# projet_pcb_etu_formatA4.net
KiCad netlist of a schematic drawn in Altium Designer
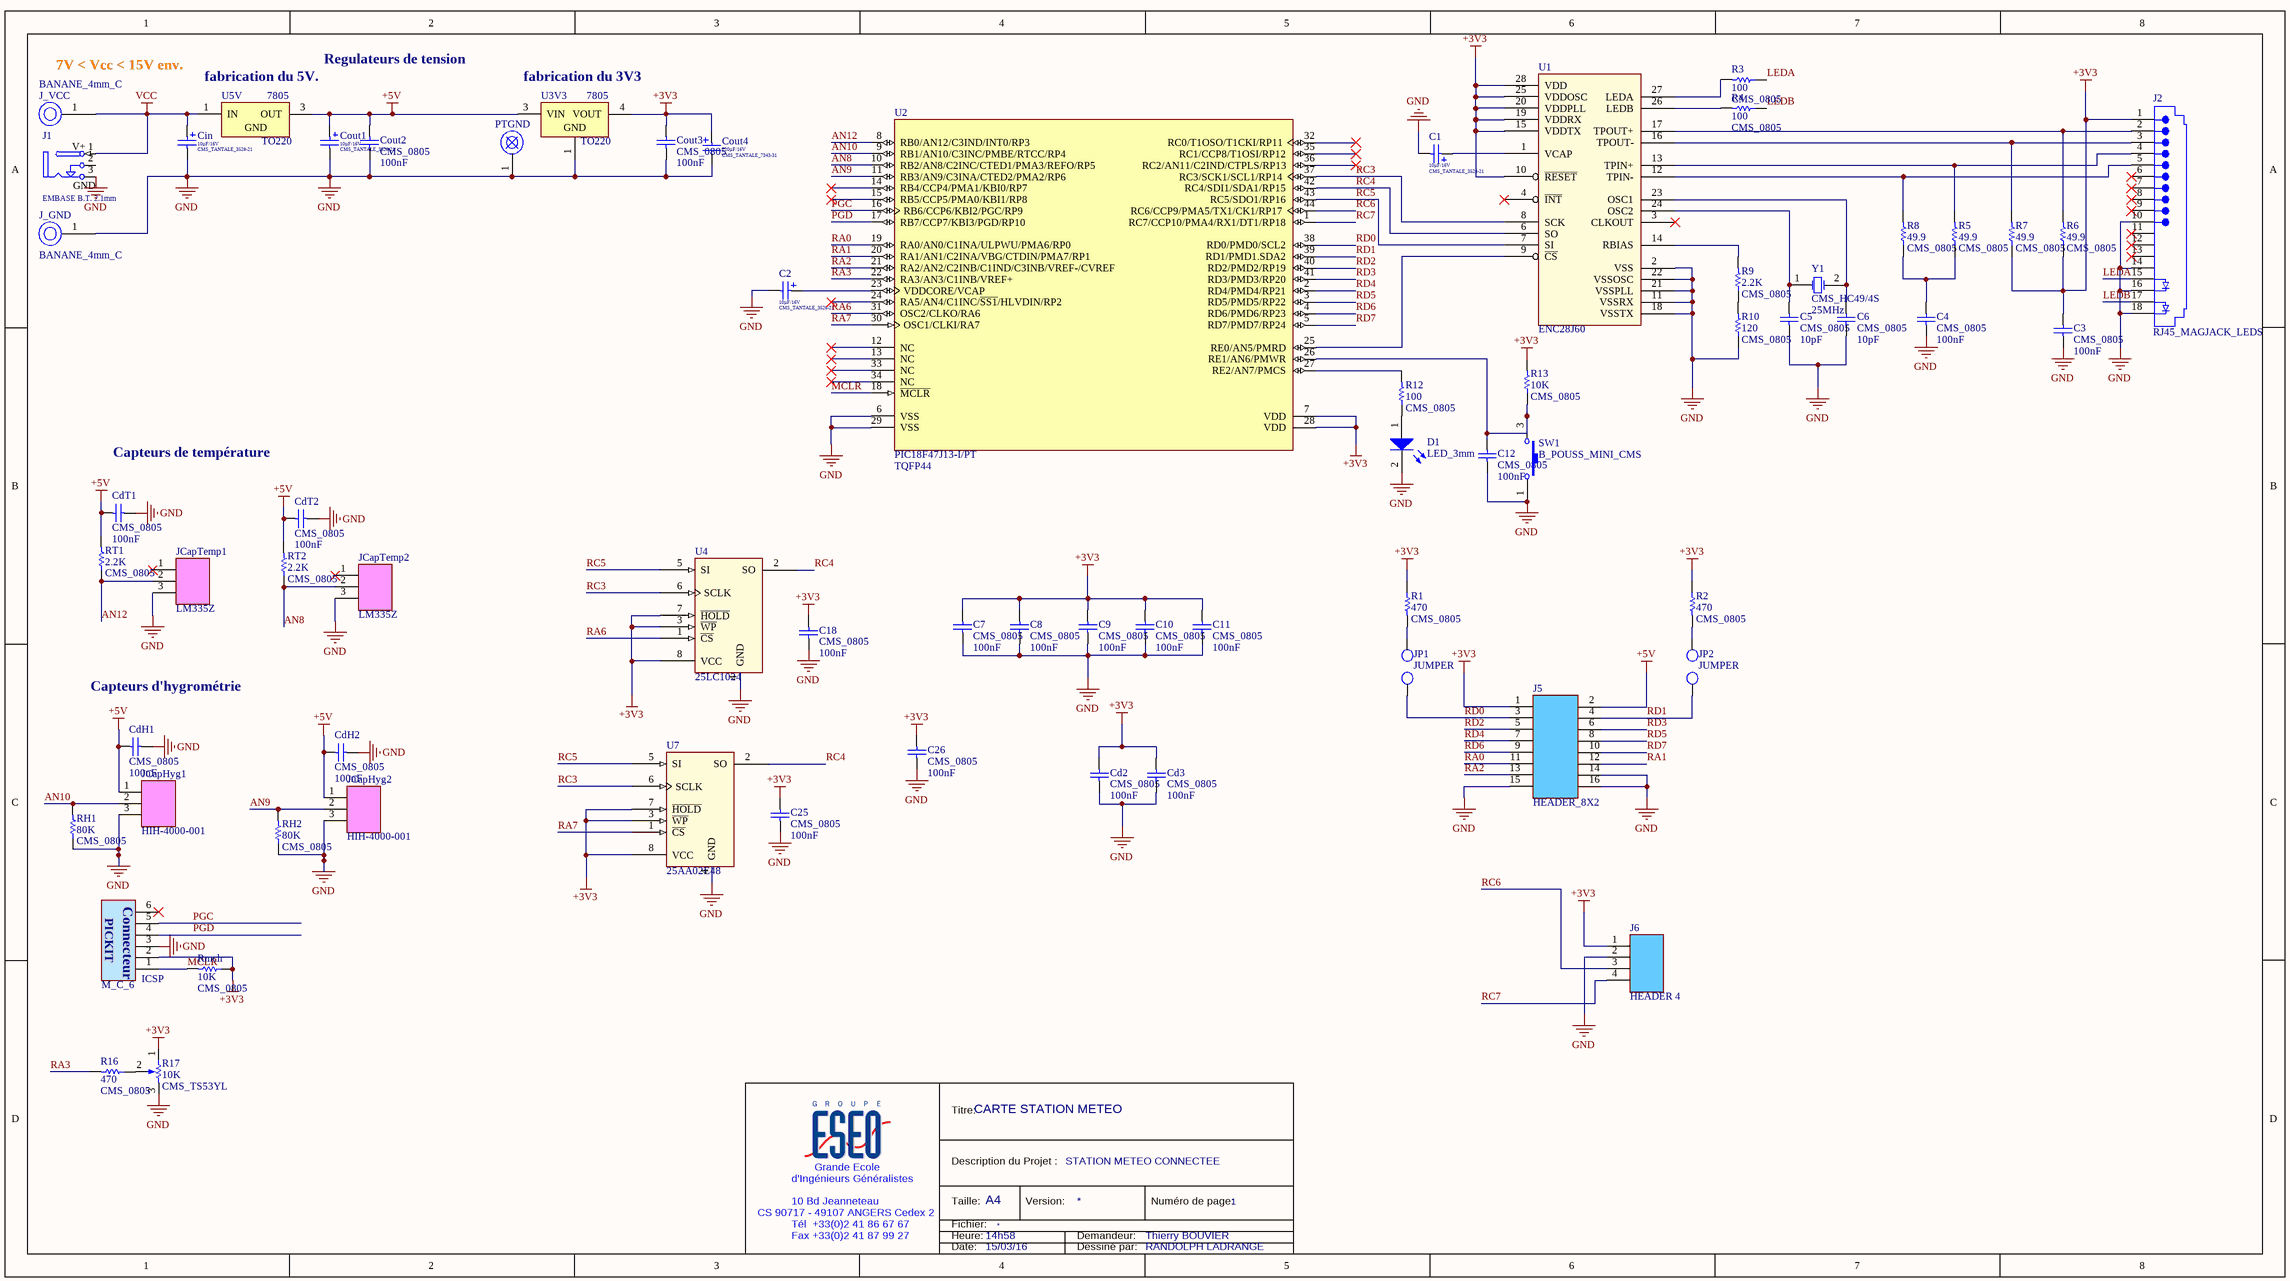
[diagram p0: projet_pcb_etu_formatA4.SchDoc]

(export (version "E")
  (design (tool "Eeschema 10.0.6"))
  (components
    (comp (ref "C1")
      (value "10µF/16V")
      (footprint "CONDENSATEUR_CMS_POLARISE_TANTALE_B/3528-21")
      (description "CONDENSATEUR CMS POLARISE TANTALE BOITIER B/3528-21")
      (fields
        (field (name "TYPE") "CMS_TANTALE_3528-21")
        (field (name "Comment") "CMS_POLARISE_TANTALE_3528-21")
      )
      (libsource (lib "composants passifs") (part "CONDENSATEUR_CMS_POL_TANT_B_3528-21"))
    )
    (comp (ref "C2")
      (value "10µF/16V")
      (footprint "CONDENSATEUR_CMS_POLARISE_TANTALE_B/3528-21")
      (description "CONDENSATEUR CMS POLARISE TANTALE BOITIER B/3528-21")
      (fields
        (field (name "TYPE") "CMS_TANTALE_3528-21")
        (field (name "Comment") "CMS_POLARISE_TANTALE_3528-21")
      )
      (libsource (lib "composants passifs") (part "CONDENSATEUR_CMS_POL_TANT_B_3528-21"))
    )
    (comp (ref "C3")
      (value "100nF")
      (footprint "CONDENSATEUR_CMS_0805")
      (description "CONDENSATEUR CMS CERAMIQUE 0805")
      (fields (field (name "TYPE") "CMS_0805") (field (name "Comment") "CMS_0805"))
      (libsource (lib "composants passifs") (part "CONDENSATEUR_CMS_CER_0805"))
    )
    (comp (ref "C4")
      (value "100nF")
      (footprint "CONDENSATEUR_CMS_0805")
      (description "CONDENSATEUR CMS CERAMIQUE 0805")
      (fields (field (name "TYPE") "CMS_0805") (field (name "Comment") "CMS_0805"))
      (libsource (lib "composants passifs") (part "CONDENSATEUR_CMS_CER_0805"))
    )
    (comp (ref "C5")
      (value "10pF")
      (footprint "CONDENSATEUR_CMS_0805")
      (description "CONDENSATEUR CMS CERAMIQUE 0805")
      (fields (field (name "TYPE") "CMS_0805") (field (name "Comment") "CMS_0805"))
      (libsource (lib "composants passifs") (part "CONDENSATEUR_CMS_CER_0805"))
    )
    (comp (ref "C6")
      (value "10pF")
      (footprint "CONDENSATEUR_CMS_0805")
      (description "CONDENSATEUR CMS CERAMIQUE 0805")
      (fields (field (name "TYPE") "CMS_0805") (field (name "Comment") "CMS_0805"))
      (libsource (lib "composants passifs") (part "CONDENSATEUR_CMS_CER_0805"))
    )
    (comp (ref "C7")
      (value "100nF")
      (footprint "CONDENSATEUR_CMS_0805")
      (description "CONDENSATEUR CMS CERAMIQUE 0805")
      (fields (field (name "TYPE") "CMS_0805") (field (name "Comment") "CMS_0805"))
      (libsource (lib "composants passifs") (part "CONDENSATEUR_CMS_CER_0805"))
    )
    (comp (ref "C8")
      (value "100nF")
      (footprint "CONDENSATEUR_CMS_0805")
      (description "CONDENSATEUR CMS CERAMIQUE 0805")
      (fields (field (name "TYPE") "CMS_0805") (field (name "Comment") "CMS_0805"))
      (libsource (lib "composants passifs") (part "CONDENSATEUR_CMS_CER_0805"))
    )
    (comp (ref "C9")
      (value "100nF")
      (footprint "CONDENSATEUR_CMS_0805")
      (description "CONDENSATEUR CMS CERAMIQUE 0805")
      (fields (field (name "TYPE") "CMS_0805") (field (name "Comment") "CMS_0805"))
      (libsource (lib "composants passifs") (part "CONDENSATEUR_CMS_CER_0805"))
    )
    (comp (ref "C10")
      (value "100nF")
      (footprint "CONDENSATEUR_CMS_0805")
      (description "CONDENSATEUR CMS CERAMIQUE 0805")
      (fields (field (name "TYPE") "CMS_0805") (field (name "Comment") "CMS_0805"))
      (libsource (lib "composants passifs") (part "CONDENSATEUR_CMS_CER_0805"))
    )
    (comp (ref "C11")
      (value "100nF")
      (footprint "CONDENSATEUR_CMS_0805")
      (description "CONDENSATEUR CMS CERAMIQUE 0805")
      (fields (field (name "TYPE") "CMS_0805") (field (name "Comment") "CMS_0805"))
      (libsource (lib "composants passifs") (part "CONDENSATEUR_CMS_CER_0805"))
    )
    (comp (ref "C12")
      (value "100nF")
      (footprint "CONDENSATEUR_CMS_0805")
      (description "CONDENSATEUR CMS CERAMIQUE 0805")
      (fields (field (name "TYPE") "CMS_0805") (field (name "Comment") "CMS_0805"))
      (libsource (lib "composants passifs") (part "CONDENSATEUR_CMS_CER_0805"))
    )
    (comp (ref "C18")
      (value "100nF")
      (footprint "CONDENSATEUR_CMS_0805")
      (description "CONDENSATEUR CMS CERAMIQUE 0805")
      (fields (field (name "TYPE") "CMS_0805") (field (name "Comment") "CMS_0805"))
      (libsource (lib "composants passifs") (part "CONDENSATEUR_CMS_CER_0805"))
    )
    (comp (ref "C25")
      (value "100nF")
      (footprint "CONDENSATEUR_CMS_0805")
      (description "CONDENSATEUR CMS CERAMIQUE 0805")
      (fields (field (name "TYPE") "CMS_0805") (field (name "Comment") "CMS_0805"))
      (libsource (lib "composants passifs") (part "CONDENSATEUR_CMS_CER_0805"))
    )
    (comp (ref "C26")
      (value "100nF")
      (footprint "CONDENSATEUR_CMS_0805")
      (description "CONDENSATEUR CMS CERAMIQUE 0805")
      (fields (field (name "TYPE") "CMS_0805") (field (name "Comment") "CMS_0805"))
      (libsource (lib "composants passifs") (part "CONDENSATEUR_CMS_CER_0805"))
    )
    (comp (ref "Cd2")
      (value "100nF")
      (footprint "CONDENSATEUR_CMS_0805")
      (description "CONDENSATEUR CMS CERAMIQUE 0805")
      (fields (field (name "TYPE") "CMS_0805") (field (name "Comment") "CMS_0805"))
      (libsource (lib "composants passifs") (part "CONDENSATEUR_CMS_CER_0805"))
    )
    (comp (ref "Cd3")
      (value "100nF")
      (footprint "CONDENSATEUR_CMS_0805")
      (description "CONDENSATEUR CMS CERAMIQUE 0805")
      (fields (field (name "TYPE") "CMS_0805") (field (name "Comment") "CMS_0805"))
      (libsource (lib "composants passifs") (part "CONDENSATEUR_CMS_CER_0805"))
    )
    (comp (ref "CdH1")
      (value "100nF")
      (footprint "CONDENSATEUR_CMS_0805")
      (description "CONDENSATEUR CMS CERAMIQUE 0805")
      (fields (field (name "TYPE") "CMS_0805") (field (name "Comment") "CMS_0805"))
      (libsource (lib "composants passifs") (part "CONDENSATEUR_CMS_CER_0805"))
    )
    (comp (ref "CdH2")
      (value "100nF")
      (footprint "CONDENSATEUR_CMS_0805")
      (description "CONDENSATEUR CMS CERAMIQUE 0805")
      (fields (field (name "TYPE") "CMS_0805") (field (name "Comment") "CMS_0805"))
      (libsource (lib "composants passifs") (part "CONDENSATEUR_CMS_CER_0805"))
    )
    (comp (ref "CdT1")
      (value "100nF")
      (footprint "CONDENSATEUR_CMS_0805")
      (description "CONDENSATEUR CMS CERAMIQUE 0805")
      (fields (field (name "TYPE") "CMS_0805") (field (name "Comment") "CMS_0805"))
      (libsource (lib "composants passifs") (part "CONDENSATEUR_CMS_CER_0805"))
    )
    (comp (ref "CdT2")
      (value "100nF")
      (footprint "CONDENSATEUR_CMS_0805")
      (description "CONDENSATEUR CMS CERAMIQUE 0805")
      (fields (field (name "TYPE") "CMS_0805") (field (name "Comment") "CMS_0805"))
      (libsource (lib "composants passifs") (part "CONDENSATEUR_CMS_CER_0805"))
    )
    (comp (ref "Cin")
      (value "10µF/16V")
      (footprint "composants passifs:CONDENSATEUR_CMS_POLARISE_TANTALE_B/3528-21")
      (description "CONDENSATEUR CMS POLARISE TANTALE BOITIER B/3528-21")
      (fields
        (field (name "TYPE") "CMS_TANTALE_3528-21")
        (field (name "Comment") "CMS_POLARISE_TANTALE_3528-21")
      )
      (libsource (lib "composants passifs") (part "CONDENSATEUR_CMS_POL_TANT_B_3528-21"))
    )
    (comp (ref "Cout1")
      (value "10µF/16V")
      (footprint "composants passifs:CONDENSATEUR_CMS_POLARISE_TANTALE_B/3528-21")
      (description "CONDENSATEUR CMS POLARISE TANTALE BOITIER B/3528-21")
      (fields
        (field (name "TYPE") "CMS_TANTALE_3528-21")
        (field (name "Comment") "CMS_POLARISE_TANTALE_3528-21")
      )
      (libsource (lib "composants passifs") (part "CONDENSATEUR_CMS_POL_TANT_B_3528-21"))
    )
    (comp (ref "Cout2")
      (value "100nF")
      (footprint "CONDENSATEUR_CMS_0805")
      (description "CONDENSATEUR CMS CERAMIQUE 0805")
      (fields (field (name "TYPE") "CMS_0805") (field (name "Comment") "CMS_0805"))
      (libsource (lib "composants passifs") (part "CONDENSATEUR_CMS_CER_0805"))
    )
    (comp (ref "Cout3")
      (value "100nF")
      (footprint "CONDENSATEUR_CMS_0805")
      (description "CONDENSATEUR CMS CERAMIQUE 0805")
      (fields (field (name "TYPE") "CMS_0805") (field (name "Comment") "CMS_0805"))
      (libsource (lib "composants passifs") (part "CONDENSATEUR_CMS_CER_0805"))
    )
    (comp (ref "Cout4")
      (value "220µF/16V")
      (footprint "CONDENSATEUR_CMS_POLARISE_TANTALE_D/7343-31")
      (description "CONDENSATEUR CMS POLARISE TANTALE BOITIER D/7343-31")
      (fields
        (field (name "TYPE") "CMS_TANTALE_7343-31")
        (field (name "Comment") "CMS_POLARISE_TANTALE_7343-31")
      )
      (libsource (lib "composants passifs") (part "CONDENSATEUR_CMS_POL_TANT_D_7343-31"))
    )
    (comp (ref "D1")
      (value "LED_3MM")
      (footprint "LED_3MM")
      (description "LED 3MM - ROUGE/VERTE/JAUNE")
      (fields (field (name "TYPE") "LED_3mm"))
      (libsource (lib "affichage") (part "LED_3MM"))
    )
    (comp (ref "ICSP")
      (value "BARRETTE_6 CONTACTS_1 RANGEE_MALE_COUDEE")
      (footprint "BARRETTE_6_M_C")
      (description "BARRETTE 6 CONTACTS 1 RANGEE MALE COUDEE")
      (fields (field (name "TYPE") "M_C_6"))
      (libsource (lib "connecteurs") (part "BARRETTE_6 CONTACTS_1 RANGEE_MALE_COUDEE"))
    )
    (comp (ref "J1")
      (value "EMBASE_BASSE_TENSION_2.1mm")
      (footprint "EMBASE_BASSE_TENSION_2.1mm")
      (description "EMBASE BASSE TENSION 2.1mm")
      (fields (field (name "TYPE") "EMBASE B.T. 2.1mm"))
      (libsource (lib "connecteurs") (part "EMBASE_BASSE_TENSION_2.1mm"))
    )
    (comp (ref "J2")
      (value "RJ45_MAGJACK_LEDS")
      (footprint "RJ45_MAGJACK_LED")
      (description "EMBASE RJ45_MAGJACK_LEDS")
      (fields (field (name "TYPE") "RJ45_MAGJACK_LEDS"))
      (libsource (lib "connecteurs") (part "RJ45_MAGJACK_LEDS"))
    )
    (comp (ref "J5")
      (value "BARRETTE_8 CONTACTS_2 RANGEES_MALE_DROITE")
      (footprint "BARRETTE_8X2_M_D")
      (fields (field (name "TYPE") "HEADER_8X2"))
      (libsource (lib "connecteurs") (part "BARRETTE_8 CONTACTS_2 RANGEES_MALE_DROITE"))
    )
    (comp (ref "J6")
      (value "BARRETTE_4 CONTACTS_1 RANGEE_MALE_DROITE")
      (footprint "BARRETTE_4_M_D")
      (description "BARRETTE 4 CONTACTS 1 RANGEE MALE DROITE")
      (fields (field (name "TYPE") "HEADER 4"))
      (libsource (lib "connecteurs") (part "BARRETTE_4 CONTACTS_1 RANGEE_MALE_DROITE"))
    )
    (comp (ref "JCapHyg1")
      (value "BARRETTE 3 CONTACTS 1 RANGEE FEMELLE DROITE")
      (footprint "BARRETTE_3_F_D")
      (fields (field (name "TYPE") "HIH-4000-001"))
      (libsource (lib "connecteurs") (part "BARRETTE_3 CONTACTS_1 RANGEE_FEMELLE_DROITE"))
    )
    (comp (ref "JCapHyg2")
      (value "BARRETTE 3 CONTACTS 1 RANGEE FEMELLE DROITE")
      (footprint "BARRETTE_3_F_D")
      (fields (field (name "TYPE") "HIH-4000-001"))
      (libsource (lib "connecteurs") (part "BARRETTE_3 CONTACTS_1 RANGEE_FEMELLE_DROITE"))
    )
    (comp (ref "JCapTemp1")
      (value "BARRETTE 3 CONTACTS 1 RANGEE FEMELLE DROITE")
      (footprint "BARRETTE_3_F_D")
      (fields (field (name "TYPE") "LM335Z"))
      (libsource (lib "connecteurs") (part "BARRETTE_3 CONTACTS_1 RANGEE_FEMELLE_DROITE"))
    )
    (comp (ref "JCapTemp2")
      (value "BARRETTE 3 CONTACTS 1 RANGEE FEMELLE DROITE")
      (footprint "BARRETTE_3_F_D")
      (fields (field (name "TYPE") "LM335Z"))
      (libsource (lib "connecteurs") (part "BARRETTE_3 CONTACTS_1 RANGEE_FEMELLE_DROITE"))
    )
    (comp (ref "JP1")
      (value "JUMPER2")
      (footprint "BARRETTE_2_M_D")
      (description "BARRETTE 2 CONTACTS 1 RANGEE MALE DROITE")
      (fields (field (name "TYPE") "JUMPER"))
      (libsource (lib "connecteurs") (part "JUMPER2"))
    )
    (comp (ref "JP2")
      (value "JUMPER2")
      (footprint "BARRETTE_2_M_D")
      (description "BARRETTE 2 CONTACTS 1 RANGEE MALE DROITE")
      (fields (field (name "TYPE") "JUMPER"))
      (libsource (lib "connecteurs") (part "JUMPER2"))
    )
    (comp (ref "J_GND")
      (value "DOUILLE BANANE 4mm COUDEE")
      (footprint "DOUILLE_BANANE_4MM_COUDEE")
      (description "DOUILLE BANANE 4 mm COUDEE")
      (fields (field (name "TYPE") "BANANE_4mm_C"))
      (libsource (lib "connecteurs") (part "DOUILLE_BANANE_4mm_COUDEE"))
    )
    (comp (ref "J_VCC")
      (value "DOUILLE BANANE 4mm COUDEE")
      (footprint "DOUILLE_BANANE_4MM_COUDEE")
      (description "DOUILLE BANANE 4 mm COUDEE")
      (fields (field (name "TYPE") "BANANE_4mm_C"))
      (libsource (lib "connecteurs") (part "DOUILLE_BANANE_4mm_COUDEE"))
    )
    (comp (ref "PTGND")
      (value "POINT_TEST")
      (footprint "POINT_TEST")
      (description "POINT TEST")
      (libsource (lib "connecteurs") (part "POINT_TEST"))
    )
    (comp (ref "R1")
      (value "470")
      (footprint "RESISTANCE_CMS_0805")
      (description "RESISTANCE CMS 0805")
      (fields (field (name "TYPE") "CMS_0805") (field (name "Comment") "RESISTANCE_CMS_0805"))
      (libsource (lib "composants passifs") (part "RESISTANCE_CMS_0805"))
    )
    (comp (ref "R2")
      (value "470")
      (footprint "RESISTANCE_CMS_0805")
      (description "RESISTANCE CMS 0805")
      (fields (field (name "TYPE") "CMS_0805") (field (name "Comment") "RESISTANCE_CMS_0805"))
      (libsource (lib "composants passifs") (part "RESISTANCE_CMS_0805"))
    )
    (comp (ref "R3")
      (value "100")
      (footprint "RESISTANCE_CMS_0805")
      (description "RESISTANCE CMS 0805")
      (fields (field (name "TYPE") "CMS_0805") (field (name "Comment") "RESISTANCE_CMS_0805"))
      (libsource (lib "composants passifs") (part "RESISTANCE_CMS_0805"))
    )
    (comp (ref "R4")
      (value "100")
      (footprint "RESISTANCE_CMS_0805")
      (description "RESISTANCE CMS 0805")
      (fields (field (name "TYPE") "CMS_0805") (field (name "Comment") "RESISTANCE_CMS_0805"))
      (libsource (lib "composants passifs") (part "RESISTANCE_CMS_0805"))
    )
    (comp (ref "R5")
      (value "49.9")
      (footprint "RESISTANCE_CMS_0805")
      (description "RESISTANCE CMS 0805")
      (fields (field (name "TYPE") "CMS_0805") (field (name "Comment") "RESISTANCE_CMS_0805"))
      (libsource (lib "composants passifs") (part "RESISTANCE_CMS_0805"))
    )
    (comp (ref "R6")
      (value "49.9")
      (footprint "RESISTANCE_CMS_0805")
      (description "RESISTANCE CMS 0805")
      (fields (field (name "TYPE") "CMS_0805") (field (name "Comment") "RESISTANCE_CMS_0805"))
      (libsource (lib "composants passifs") (part "RESISTANCE_CMS_0805"))
    )
    (comp (ref "R7")
      (value "49.9")
      (footprint "RESISTANCE_CMS_0805")
      (description "RESISTANCE CMS 0805")
      (fields (field (name "TYPE") "CMS_0805") (field (name "Comment") "RESISTANCE_CMS_0805"))
      (libsource (lib "composants passifs") (part "RESISTANCE_CMS_0805"))
    )
    (comp (ref "R8")
      (value "49.9")
      (footprint "RESISTANCE_CMS_0805")
      (description "RESISTANCE CMS 0805")
      (fields (field (name "TYPE") "CMS_0805") (field (name "Comment") "RESISTANCE_CMS_0805"))
      (libsource (lib "composants passifs") (part "RESISTANCE_CMS_0805"))
    )
    (comp (ref "R9")
      (value "2.2K")
      (footprint "RESISTANCE_CMS_0805")
      (description "RESISTANCE CMS 0805")
      (fields (field (name "TYPE") "CMS_0805") (field (name "Comment") "RESISTANCE_CMS_0805"))
      (libsource (lib "composants passifs") (part "RESISTANCE_CMS_0805"))
    )
    (comp (ref "R10")
      (value "120")
      (footprint "RESISTANCE_CMS_0805")
      (description "RESISTANCE CMS 0805")
      (fields (field (name "TYPE") "CMS_0805") (field (name "Comment") "RESISTANCE_CMS_0805"))
      (libsource (lib "composants passifs") (part "RESISTANCE_CMS_0805"))
    )
    (comp (ref "R12")
      (value "100")
      (footprint "RESISTANCE_CMS_0805")
      (description "RESISTANCE CMS 0805")
      (fields (field (name "TYPE") "CMS_0805") (field (name "Comment") "RESISTANCE_CMS_0805"))
      (libsource (lib "composants passifs") (part "RESISTANCE_CMS_0805"))
    )
    (comp (ref "R13")
      (value "10K")
      (footprint "RESISTANCE_CMS_0805")
      (description "RESISTANCE CMS 0805")
      (fields (field (name "TYPE") "CMS_0805") (field (name "Comment") "RESISTANCE_CMS_0805"))
      (libsource (lib "composants passifs") (part "RESISTANCE_CMS_0805"))
    )
    (comp (ref "R16")
      (value "470")
      (footprint "RESISTANCE_CMS_0805")
      (description "RESISTANCE CMS 0805")
      (fields (field (name "TYPE") "CMS_0805") (field (name "Comment") "RESISTANCE_CMS_0805"))
      (libsource (lib "composants passifs") (part "RESISTANCE_CMS_0805"))
    )
    (comp (ref "R17")
      (value "10K")
      (footprint "TRIMMER_CMS_TS53YL")
      (description "RESISTANCE VARIABLE_CMS : TS53YL")
      (fields (field (name "TYPE") "CMS_TS53YL") (field (name "Comment") "RESISTANCE_VARIABLE_CMS : TS53YL"))
      (libsource (lib "composants passifs") (part "RESISTANCE_VARIABLE_CMS {colon} TS53YL"))
    )
    (comp (ref "RH1")
      (value "80K")
      (footprint "RESISTANCE_CMS_0805")
      (description "RESISTANCE CMS 0805")
      (fields (field (name "TYPE") "CMS_0805") (field (name "Comment") "RESISTANCE_CMS_0805"))
      (libsource (lib "composants passifs") (part "RESISTANCE_CMS_0805"))
    )
    (comp (ref "RH2")
      (value "80K")
      (footprint "RESISTANCE_CMS_0805")
      (description "RESISTANCE CMS 0805")
      (fields (field (name "TYPE") "CMS_0805") (field (name "Comment") "RESISTANCE_CMS_0805"))
      (libsource (lib "composants passifs") (part "RESISTANCE_CMS_0805"))
    )
    (comp (ref "Rmclr")
      (value "10K")
      (footprint "RESISTANCE_CMS_0805")
      (description "RESISTANCE CMS 0805")
      (fields (field (name "TYPE") "CMS_0805") (field (name "Comment") "RESISTANCE_CMS_0805"))
      (libsource (lib "composants passifs") (part "RESISTANCE_CMS_0805"))
    )
    (comp (ref "RT1")
      (value "2.2K")
      (footprint "RESISTANCE_CMS_0805")
      (description "RESISTANCE CMS 0805")
      (fields (field (name "TYPE") "CMS_0805") (field (name "Comment") "RESISTANCE_CMS_0805"))
      (libsource (lib "composants passifs") (part "RESISTANCE_CMS_0805"))
    )
    (comp (ref "RT2")
      (value "2.2K")
      (footprint "RESISTANCE_CMS_0805")
      (description "RESISTANCE CMS 0805")
      (fields (field (name "TYPE") "CMS_0805") (field (name "Comment") "RESISTANCE_CMS_0805"))
      (libsource (lib "composants passifs") (part "RESISTANCE_CMS_0805"))
    )
    (comp (ref "SW1")
      (value "BOUTON_POUSSOIR_MINIATURE_CMS")
      (footprint "BOUTON_POUSS_CMS")
      (description "BOUTON POUSSOIR MINIATURE CMS ON/OFF")
      (fields (field (name "TYPE") "B_POUSS_MINI_CMS"))
      (libsource (lib "commutation") (part "BOUTON_POUSSOIR_MINIATURE_CMS"))
    )
    (comp (ref "U1")
      (value "ENC28J60")
      (footprint "circuits integres:SOIC28_PAS=1.27_LARG=10.3_LONG=18")
      (libsource (lib "circuits integres") (part "ENC28J60"))
    )
    (comp (ref "U2")
      (value "PIC18F47J13-I/PT_TQFP44")
      (footprint "TQFP44_PAS=0.8_LARG=12_LONG=12")
      (fields (field (name "TYPE") "PIC18F47J13-I/PT") (field (name "PACKAGE") "TQFP44"))
      (libsource (lib "circuits integres") (part "PIC18F47J13-I/PT_TQFP44"))
    )
    (comp (ref "U3V3")
      (value "REGULATEUR_TO220_78XX")
      (footprint "composants actifs:TO-252")
      (description "REGULATEUR DE TENSION POSITIVE 78XX BOITIER TO220")
      (fields (field (name "TYPE") "7805") (field (name "PACKAGE") "TO220"))
      (libsource (lib "") (part "REGULATEUR_TO220_78XX_1"))
    )
    (comp (ref "U4")
      (value "25LC1024")
      (footprint "SOP8_PAS=1.27_LARG=6_LONG=5.2")
      (libsource (lib "circuits integres") (part "25LC1024"))
    )
    (comp (ref "U5V")
      (value "REGULATEUR_TO220_78XX")
      (footprint "composants actifs:TO-252")
      (description "REGULATEUR DE TENSION POSITIVE 78XX BOITIER TO220")
      (fields (field (name "TYPE") "7805") (field (name "PACKAGE") "TO220"))
      (libsource (lib "composants actifs") (part "REGULATEUR_TO220_78XX"))
    )
    (comp (ref "U7")
      (value "25AA02E48")
      (footprint "SOIC8_PAS=1.27_LARG=4_LONG=5")
      (libsource (lib "circuits integres") (part "25AA02E48"))
    )
    (comp (ref "Y1")
      (value "25MHz")
      (footprint "QUARTZ_CMS_HC49/4S")
      (description "QUARTZ CMS HC49/4S")
      (fields (field (name "TYPE") "CMS_HC49/4S") (field (name "Comment") "QUARTZ_CMS_HC49/4S"))
      (libsource (lib "composants passifs") (part "QUARTZ_CMS_HC49/4S"))
    )
  )
  (nets
    (net (code "1") (name "+3V3") (class "Default")
      (node (ref "C10") (pin "1") (pinfunction "1_1") (pintype "passive"))
      (node (ref "C11") (pin "1") (pinfunction "1_1") (pintype "passive"))
      (node (ref "C18") (pin "2") (pinfunction "2_2") (pintype "passive"))
      (node (ref "C25") (pin "2") (pinfunction "2_2") (pintype "passive"))
      (node (ref "C26") (pin "2") (pinfunction "2_2") (pintype "passive"))
      (node (ref "C3") (pin "1") (pinfunction "1_1") (pintype "passive"))
      (node (ref "C7") (pin "1") (pinfunction "1_1") (pintype "passive"))
      (node (ref "C8") (pin "1") (pinfunction "1_1") (pintype "passive"))
      (node (ref "C9") (pin "1") (pinfunction "1_1") (pintype "passive"))
      (node (ref "Cd2") (pin "1") (pinfunction "1_1") (pintype "passive"))
      (node (ref "Cd3") (pin "1") (pinfunction "1_1") (pintype "passive"))
      (node (ref "Cout3") (pin "1") (pinfunction "1_1") (pintype "passive"))
      (node (ref "Cout4") (pin "1") (pinfunction "1_1") (pintype "passive"))
      (node (ref "ICSP") (pin "2") (pinfunction "2_2") (pintype "passive"))
      (node (ref "J2") (pin "1") (pinfunction "1_1") (pintype "passive"))
      (node (ref "J5") (pin "1") (pinfunction "1_1") (pintype "passive"))
      (node (ref "J6") (pin "1") (pinfunction "1_1") (pintype "passive"))
      (node (ref "R1") (pin "1") (pinfunction "1_1") (pintype "passive"))
      (node (ref "R13") (pin "2") (pinfunction "2_2") (pintype "passive"))
      (node (ref "R17") (pin "1") (pinfunction "1_1") (pintype "passive"))
      (node (ref "R2") (pin "1") (pinfunction "1_1") (pintype "passive"))
      (node (ref "R6") (pin "1") (pinfunction "1_1") (pintype "passive"))
      (node (ref "R7") (pin "1") (pinfunction "1_1") (pintype "passive"))
      (node (ref "Rmclr") (pin "1") (pinfunction "1_1") (pintype "passive"))
      (node (ref "U1") (pin "10") (pinfunction "~{RESET}_10") (pintype "passive"))
      (node (ref "U1") (pin "15") (pinfunction "VDDTX_15") (pintype "passive"))
      (node (ref "U1") (pin "19") (pinfunction "VDDRX_19") (pintype "passive"))
      (node (ref "U1") (pin "20") (pinfunction "VDDPLL_20") (pintype "passive"))
      (node (ref "U1") (pin "25") (pinfunction "VDDOSC_25") (pintype "passive"))
      (node (ref "U1") (pin "28") (pinfunction "VDD_28") (pintype "passive"))
      (node (ref "U2") (pin "28") (pinfunction "VDD_28") (pintype "power_in"))
      (node (ref "U2") (pin "7") (pinfunction "VDD_7") (pintype "power_in"))
      (node (ref "U3V3") (pin "4") (pinfunction "VOUT_4") (pintype "power_in"))
      (node (ref "U4") (pin "3") (pinfunction "~{WP}_3") (pintype "input"))
      (node (ref "U4") (pin "7") (pinfunction "~{HOLD}_7") (pintype "input"))
      (node (ref "U4") (pin "8") (pinfunction "VCC_8") (pintype "power_in"))
      (node (ref "U7") (pin "3") (pinfunction "~{WP}_3") (pintype "input"))
      (node (ref "U7") (pin "7") (pinfunction "~{HOLD}_7") (pintype "input"))
      (node (ref "U7") (pin "8") (pinfunction "VCC_8") (pintype "power_in"))
    )
    (net (code "2") (name "+5V") (class "Default")
      (node (ref "CdH1") (pin "1") (pinfunction "1_1") (pintype "passive"))
      (node (ref "CdH2") (pin "1") (pinfunction "1_1") (pintype "passive"))
      (node (ref "CdT1") (pin "1") (pinfunction "1_1") (pintype "passive"))
      (node (ref "CdT2") (pin "1") (pinfunction "1_1") (pintype "passive"))
      (node (ref "Cout1") (pin "1") (pinfunction "1_1") (pintype "passive"))
      (node (ref "Cout2") (pin "1") (pinfunction "1_1") (pintype "passive"))
      (node (ref "J5") (pin "2") (pinfunction "2_2") (pintype "passive"))
      (node (ref "JCapHyg1") (pin "1") (pinfunction "1_1") (pintype "passive"))
      (node (ref "JCapHyg2") (pin "1") (pinfunction "1_1") (pintype "passive"))
      (node (ref "RT1") (pin "2") (pinfunction "2_2") (pintype "passive"))
      (node (ref "RT2") (pin "2") (pinfunction "2_2") (pintype "passive"))
      (node (ref "U3V3") (pin "3") (pinfunction "VIN_3") (pintype "power_in"))
      (node (ref "U5V") (pin "3") (pinfunction "OUT_3") (pintype "power_in"))
    )
    (net (code "3") (name "/AN8") (class "Default")
      (node (ref "JCapTemp2") (pin "2") (pinfunction "2_2") (pintype "passive"))
      (node (ref "RT2") (pin "1") (pinfunction "1_1") (pintype "passive"))
      (node (ref "U2") (pin "10") (pinfunction "RB2/AN8/C2INC/CTED1/PMA3/REFO/RP5_10") (pintype "bidirectional"))
    )
    (net (code "4") (name "/AN9") (class "Default")
      (node (ref "JCapHyg2") (pin "2") (pinfunction "2_2") (pintype "passive"))
      (node (ref "RH2") (pin "2") (pinfunction "2_2") (pintype "passive"))
      (node (ref "U2") (pin "11") (pinfunction "RB3/AN9/C3INA/CTED2/PMA2/RP6_11") (pintype "bidirectional"))
    )
    (net (code "5") (name "/AN10") (class "Default")
      (node (ref "JCapHyg1") (pin "2") (pinfunction "2_2") (pintype "passive"))
      (node (ref "RH1") (pin "2") (pinfunction "2_2") (pintype "passive"))
      (node (ref "U2") (pin "9") (pinfunction "RB1/AN10/C3INC/PMBE/RTCC/RP4_9") (pintype "bidirectional"))
    )
    (net (code "6") (name "/AN12") (class "Default")
      (node (ref "JCapTemp1") (pin "2") (pinfunction "2_2") (pintype "passive"))
      (node (ref "RT1") (pin "1") (pinfunction "1_1") (pintype "passive"))
      (node (ref "U2") (pin "8") (pinfunction "RB0/AN12/C3IND/INT0/RP3_8") (pintype "bidirectional"))
    )
    (net (code "7") (name "/LEDA") (class "Default")
      (node (ref "J2") (pin "15") (pinfunction "15_15") (pintype "passive"))
      (node (ref "R3") (pin "1") (pinfunction "1_1") (pintype "passive"))
    )
    (net (code "8") (name "/LEDB") (class "Default")
      (node (ref "J2") (pin "17") (pinfunction "17_17") (pintype "passive"))
      (node (ref "R4") (pin "1") (pinfunction "1_1") (pintype "passive"))
    )
    (net (code "9") (name "/MCLR") (class "Default")
      (node (ref "ICSP") (pin "1") (pinfunction "1_1") (pintype "passive"))
      (node (ref "Rmclr") (pin "2") (pinfunction "2_2") (pintype "passive"))
      (node (ref "U2") (pin "18") (pinfunction "~{MCLR}_18") (pintype "input"))
    )
    (net (code "10") (name "/PGC") (class "Default")
      (node (ref "ICSP") (pin "5") (pinfunction "5_5") (pintype "passive"))
      (node (ref "U2") (pin "16") (pinfunction "RB6/CCP6/KBI2/PGC/RP9_16") (pintype "bidirectional"))
    )
    (net (code "11") (name "/PGD") (class "Default")
      (node (ref "ICSP") (pin "4") (pinfunction "4_4") (pintype "passive"))
      (node (ref "U2") (pin "17") (pinfunction "RB7/CCP7/KBI3/PGD/RP10_17") (pintype "bidirectional"))
    )
    (net (code "12") (name "/RA0") (class "Default")
      (node (ref "J5") (pin "11") (pinfunction "11_11") (pintype "passive"))
      (node (ref "U2") (pin "19") (pinfunction "RA0/AN0/C1INA/ULPWU/PMA6/RP0_19") (pintype "bidirectional"))
    )
    (net (code "13") (name "/RA1") (class "Default")
      (node (ref "J5") (pin "12") (pinfunction "12_12") (pintype "passive"))
      (node (ref "U2") (pin "20") (pinfunction "RA1/AN1/C2INA/VBG/CTDIN/PMA7/RP1_20") (pintype "bidirectional"))
    )
    (net (code "14") (name "/RA2") (class "Default")
      (node (ref "J5") (pin "13") (pinfunction "13_13") (pintype "passive"))
      (node (ref "U2") (pin "21") (pinfunction "RA2/AN2/C2INB/C1IND/C3INB/VREF-/CVREF_21") (pintype "bidirectional"))
    )
    (net (code "15") (name "/RA3") (class "Default")
      (node (ref "R16") (pin "2") (pinfunction "2_2") (pintype "passive"))
      (node (ref "U2") (pin "22") (pinfunction "RA3/AN3/C1INB/VREF+_22") (pintype "bidirectional"))
    )
    (net (code "16") (name "/RA6") (class "Default")
      (node (ref "U2") (pin "31") (pinfunction "OSC2/CLKO/RA6_31") (pintype "bidirectional"))
      (node (ref "U4") (pin "1") (pinfunction "~{CS}_1") (pintype "input"))
    )
    (net (code "17") (name "/RA7") (class "Default")
      (node (ref "U2") (pin "30") (pinfunction "OSC1/CLKI/RA7_30") (pintype "input"))
      (node (ref "U7") (pin "1") (pinfunction "~{CS}_1") (pintype "input"))
    )
    (net (code "18") (name "/RC3") (class "Default")
      (node (ref "U1") (pin "8") (pinfunction "SCK_8") (pintype "passive"))
      (node (ref "U2") (pin "37") (pinfunction "RC3/SCK1/SCL1/RP14_37") (pintype "bidirectional"))
      (node (ref "U4") (pin "6") (pinfunction "SCLK_6") (pintype "input"))
      (node (ref "U7") (pin "6") (pinfunction "SCLK_6") (pintype "input"))
    )
    (net (code "19") (name "/RC4") (class "Default")
      (node (ref "U1") (pin "6") (pinfunction "SO_6") (pintype "passive"))
      (node (ref "U2") (pin "42") (pinfunction "RC4/SDI1/SDA1/RP15_42") (pintype "bidirectional"))
      (node (ref "U4") (pin "2") (pinfunction "SO_2") (pintype "tri_state"))
      (node (ref "U7") (pin "2") (pinfunction "SO_2") (pintype "tri_state"))
    )
    (net (code "20") (name "/RC5") (class "Default")
      (node (ref "U1") (pin "7") (pinfunction "SI_7") (pintype "passive"))
      (node (ref "U2") (pin "43") (pinfunction "RC5/SDO1/RP16_43") (pintype "bidirectional"))
      (node (ref "U4") (pin "5") (pinfunction "SI_5") (pintype "input"))
      (node (ref "U7") (pin "5") (pinfunction "SI_5") (pintype "input"))
    )
    (net (code "21") (name "/RC6") (class "Default")
      (node (ref "J6") (pin "3") (pinfunction "3_3") (pintype "passive"))
      (node (ref "U2") (pin "44") (pinfunction "RC6/CCP9/PMA5/TX1/CK1/RP17_44") (pintype "bidirectional"))
    )
    (net (code "22") (name "/RC7") (class "Default")
      (node (ref "J6") (pin "4") (pinfunction "4_4") (pintype "passive"))
      (node (ref "U2") (pin "1") (pinfunction "RC7/CCP10/PMA4/RX1/DT1/RP18_1") (pintype "bidirectional"))
    )
    (net (code "23") (name "/RD0") (class "Default")
      (node (ref "J5") (pin "3") (pinfunction "3_3") (pintype "passive"))
      (node (ref "JP1") (pin "1") (pinfunction "1_1") (pintype "passive"))
      (node (ref "U2") (pin "38") (pinfunction "RD0/PMD0/SCL2_38") (pintype "bidirectional"))
    )
    (net (code "24") (name "/RD1") (class "Default")
      (node (ref "J5") (pin "4") (pinfunction "4_4") (pintype "passive"))
      (node (ref "JP2") (pin "1") (pinfunction "1_1") (pintype "passive"))
      (node (ref "U2") (pin "39") (pinfunction "RD1/PMD1.SDA2_39") (pintype "bidirectional"))
    )
    (net (code "25") (name "/RD2") (class "Default")
      (node (ref "J5") (pin "5") (pinfunction "5_5") (pintype "passive"))
      (node (ref "U2") (pin "40") (pinfunction "RD2/PMD2/RP19_40") (pintype "bidirectional"))
    )
    (net (code "26") (name "/RD3") (class "Default")
      (node (ref "J5") (pin "6") (pinfunction "6_6") (pintype "passive"))
      (node (ref "U2") (pin "41") (pinfunction "RD3/PMD3/RP20_41") (pintype "bidirectional"))
    )
    (net (code "27") (name "/RD4") (class "Default")
      (node (ref "J5") (pin "7") (pinfunction "7_7") (pintype "passive"))
      (node (ref "U2") (pin "2") (pinfunction "RD4/PMD4/RP21_2") (pintype "bidirectional"))
    )
    (net (code "28") (name "/RD5") (class "Default")
      (node (ref "J5") (pin "8") (pinfunction "8_8") (pintype "passive"))
      (node (ref "U2") (pin "3") (pinfunction "RD5/PMD5/RP22_3") (pintype "bidirectional"))
    )
    (net (code "29") (name "/RD6") (class "Default")
      (node (ref "J5") (pin "9") (pinfunction "9_9") (pintype "passive"))
      (node (ref "U2") (pin "4") (pinfunction "RD6/PMD6/RP23_4") (pintype "bidirectional"))
    )
    (net (code "30") (name "/RD7") (class "Default")
      (node (ref "J5") (pin "10") (pinfunction "10_10") (pintype "passive"))
      (node (ref "U2") (pin "5") (pinfunction "RD7/PMD7/RP24_5") (pintype "bidirectional"))
    )
    (net (code "31") (name "GND") (class "Default")
      (node (ref "C1") (pin "2") (pinfunction "2_2") (pintype "passive"))
      (node (ref "C10") (pin "2") (pinfunction "2_2") (pintype "passive"))
      (node (ref "C11") (pin "2") (pinfunction "2_2") (pintype "passive"))
      (node (ref "C12") (pin "2") (pinfunction "2_2") (pintype "passive"))
      (node (ref "C18") (pin "1") (pinfunction "1_1") (pintype "passive"))
      (node (ref "C2") (pin "2") (pinfunction "2_2") (pintype "passive"))
      (node (ref "C25") (pin "1") (pinfunction "1_1") (pintype "passive"))
      (node (ref "C26") (pin "1") (pinfunction "1_1") (pintype "passive"))
      (node (ref "C3") (pin "2") (pinfunction "2_2") (pintype "passive"))
      (node (ref "C4") (pin "2") (pinfunction "2_2") (pintype "passive"))
      (node (ref "C5") (pin "2") (pinfunction "2_2") (pintype "passive"))
      (node (ref "C6") (pin "2") (pinfunction "2_2") (pintype "passive"))
      (node (ref "C7") (pin "2") (pinfunction "2_2") (pintype "passive"))
      (node (ref "C8") (pin "2") (pinfunction "2_2") (pintype "passive"))
      (node (ref "C9") (pin "2") (pinfunction "2_2") (pintype "passive"))
      (node (ref "Cd2") (pin "2") (pinfunction "2_2") (pintype "passive"))
      (node (ref "Cd3") (pin "2") (pinfunction "2_2") (pintype "passive"))
      (node (ref "CdH1") (pin "2") (pinfunction "2_2") (pintype "passive"))
      (node (ref "CdH2") (pin "2") (pinfunction "2_2") (pintype "passive"))
      (node (ref "CdT1") (pin "2") (pinfunction "2_2") (pintype "passive"))
      (node (ref "CdT2") (pin "2") (pinfunction "2_2") (pintype "passive"))
      (node (ref "Cin") (pin "2") (pinfunction "2_2") (pintype "passive"))
      (node (ref "Cout1") (pin "2") (pinfunction "2_2") (pintype "passive"))
      (node (ref "Cout2") (pin "2") (pinfunction "2_2") (pintype "passive"))
      (node (ref "Cout3") (pin "2") (pinfunction "2_2") (pintype "passive"))
      (node (ref "Cout4") (pin "2") (pinfunction "2_2") (pintype "passive"))
      (node (ref "D1") (pin "2") (pinfunction "2_2") (pintype "passive"))
      (node (ref "ICSP") (pin "3") (pinfunction "3_3") (pintype "passive"))
      (node (ref "J1") (pin "3") (pinfunction "3_3") (pintype "passive"))
      (node (ref "J2") (pin "10") (pinfunction "10_10") (pintype "passive"))
      (node (ref "J2") (pin "14") (pinfunction "14_14") (pintype "passive"))
      (node (ref "J2") (pin "16") (pinfunction "16_16") (pintype "passive"))
      (node (ref "J2") (pin "18") (pinfunction "18_18") (pintype "passive"))
      (node (ref "J5") (pin "14") (pinfunction "14_14") (pintype "passive"))
      (node (ref "J5") (pin "15") (pinfunction "15_15") (pintype "passive"))
      (node (ref "J5") (pin "16") (pinfunction "16_16") (pintype "passive"))
      (node (ref "J6") (pin "2") (pinfunction "2_2") (pintype "passive"))
      (node (ref "JCapHyg1") (pin "3") (pinfunction "3_3") (pintype "passive"))
      (node (ref "JCapHyg2") (pin "3") (pinfunction "3_3") (pintype "passive"))
      (node (ref "JCapTemp1") (pin "3") (pinfunction "3_3") (pintype "passive"))
      (node (ref "JCapTemp2") (pin "3") (pinfunction "3_3") (pintype "passive"))
      (node (ref "J_GND") (pin "1") (pinfunction "1_1") (pintype "passive"))
      (node (ref "PTGND") (pin "1") (pinfunction "3_1") (pintype "passive"))
      (node (ref "R10") (pin "1") (pinfunction "1_1") (pintype "passive"))
      (node (ref "R17") (pin "3") (pinfunction "3_3") (pintype "passive"))
      (node (ref "RH1") (pin "1") (pinfunction "1_1") (pintype "passive"))
      (node (ref "RH2") (pin "1") (pinfunction "1_1") (pintype "passive"))
      (node (ref "SW1") (pin "1") (pinfunction "1_1") (pintype "passive"))
      (node (ref "U1") (pin "11") (pinfunction "VSSRX_11") (pintype "passive"))
      (node (ref "U1") (pin "18") (pinfunction "VSSTX_18") (pintype "passive"))
      (node (ref "U1") (pin "2") (pinfunction "VSS_2") (pintype "passive"))
      (node (ref "U1") (pin "21") (pinfunction "VSSPLL_21") (pintype "passive"))
      (node (ref "U1") (pin "22") (pinfunction "VSSOSC_22") (pintype "passive"))
      (node (ref "U2") (pin "29") (pinfunction "VSS_29") (pintype "power_in"))
      (node (ref "U2") (pin "6") (pinfunction "VSS_6") (pintype "power_in"))
      (node (ref "U3V3") (pin "1") (pinfunction "GND_1") (pintype "power_in"))
      (node (ref "U4") (pin "4") (pinfunction "GND_4") (pintype "power_in"))
      (node (ref "U7") (pin "4") (pinfunction "GND_4") (pintype "power_in"))
    )
    (net (code "32") (name "Net-(C4-Pad1)") (class "Default")
      (node (ref "C4") (pin "1") (pinfunction "1_1") (pintype "passive"))
      (node (ref "R5") (pin "1") (pinfunction "1_1") (pintype "passive"))
      (node (ref "R8") (pin "1") (pinfunction "1_1") (pintype "passive"))
    )
    (net (code "33") (name "Net-(D1-Pad1)") (class "Default")
      (node (ref "D1") (pin "1") (pinfunction "1_1") (pintype "passive"))
      (node (ref "R12") (pin "1") (pinfunction "1_1") (pintype "passive"))
    )
    (net (code "34") (name "Net-(JP1-Pad2)") (class "Default")
      (node (ref "JP1") (pin "2") (pinfunction "2_2") (pintype "passive"))
      (node (ref "R1") (pin "2") (pinfunction "2_2") (pintype "passive"))
    )
    (net (code "35") (name "Net-(JP2-Pad2)") (class "Default")
      (node (ref "JP2") (pin "2") (pinfunction "2_2") (pintype "passive"))
      (node (ref "R2") (pin "2") (pinfunction "2_2") (pintype "passive"))
    )
    (net (code "36") (name "Net-(R10-Pad2)") (class "Default")
      (node (ref "R10") (pin "2") (pinfunction "2_2") (pintype "passive"))
      (node (ref "R9") (pin "1") (pinfunction "1_1") (pintype "passive"))
    )
    (net (code "37") (name "Net-(R16-Pad1)") (class "Default")
      (node (ref "R16") (pin "1") (pinfunction "1_1") (pintype "passive"))
      (node (ref "R17") (pin "2") (pinfunction "2_2") (pintype "passive"))
    )
    (net (code "38") (name "Net-(U1-LEDA)") (class "Default")
      (node (ref "R3") (pin "2") (pinfunction "2_2") (pintype "passive"))
      (node (ref "U1") (pin "27") (pinfunction "LEDA_27") (pintype "passive"))
    )
    (net (code "39") (name "Net-(U1-LEDB)") (class "Default")
      (node (ref "R4") (pin "2") (pinfunction "2_2") (pintype "passive"))
      (node (ref "U1") (pin "26") (pinfunction "LEDB_26") (pintype "passive"))
    )
    (net (code "40") (name "Net-(U1-OSC1)") (class "Default")
      (node (ref "C6") (pin "1") (pinfunction "1_1") (pintype "passive"))
      (node (ref "U1") (pin "23") (pinfunction "OSC1_23") (pintype "passive"))
      (node (ref "Y1") (pin "2") (pinfunction "OSC2_2") (pintype "passive"))
    )
    (net (code "41") (name "Net-(U1-OSC2)") (class "Default")
      (node (ref "C5") (pin "1") (pinfunction "1_1") (pintype "passive"))
      (node (ref "U1") (pin "24") (pinfunction "OSC2_24") (pintype "passive"))
      (node (ref "Y1") (pin "1") (pinfunction "OSC1_1") (pintype "passive"))
    )
    (net (code "42") (name "Net-(U1-RBIAS)") (class "Default")
      (node (ref "R9") (pin "2") (pinfunction "2_2") (pintype "passive"))
      (node (ref "U1") (pin "14") (pinfunction "RBIAS_14") (pintype "passive"))
    )
    (net (code "43") (name "Net-(U1-TPIN+)") (class "Default")
      (node (ref "J2") (pin "4") (pinfunction "4_4") (pintype "passive"))
      (node (ref "R5") (pin "2") (pinfunction "2_2") (pintype "passive"))
      (node (ref "U1") (pin "13") (pinfunction "TPIN+_13") (pintype "passive"))
    )
    (net (code "44") (name "Net-(U1-TPIN-)") (class "Default")
      (node (ref "J2") (pin "5") (pinfunction "5_5") (pintype "passive"))
      (node (ref "R8") (pin "2") (pinfunction "2_2") (pintype "passive"))
      (node (ref "U1") (pin "12") (pinfunction "TPIN-_12") (pintype "passive"))
    )
    (net (code "45") (name "Net-(U1-TPOUT+)") (class "Default")
      (node (ref "J2") (pin "2") (pinfunction "2_2") (pintype "passive"))
      (node (ref "R6") (pin "2") (pinfunction "2_2") (pintype "passive"))
      (node (ref "U1") (pin "17") (pinfunction "TPOUT+_17") (pintype "passive"))
    )
    (net (code "46") (name "Net-(U1-TPOUT-)") (class "Default")
      (node (ref "J2") (pin "3") (pinfunction "3_3") (pintype "passive"))
      (node (ref "R7") (pin "2") (pinfunction "2_2") (pintype "passive"))
      (node (ref "U1") (pin "16") (pinfunction "TPOUT-_16") (pintype "passive"))
    )
    (net (code "47") (name "Net-(U1-VCAP)") (class "Default")
      (node (ref "C1") (pin "1") (pinfunction "1_1") (pintype "passive"))
      (node (ref "U1") (pin "1") (pinfunction "VCAP_1") (pintype "passive"))
    )
    (net (code "48") (name "Net-(U1-~{CS})") (class "Default")
      (node (ref "U1") (pin "9") (pinfunction "~{CS}_9") (pintype "passive"))
      (node (ref "U2") (pin "25") (pinfunction "RE0/AN5/PMRD_25") (pintype "bidirectional"))
    )
    (net (code "49") (name "Net-(U2-RE1{slash}AN6{slash}PMWR)") (class "Default")
      (node (ref "C12") (pin "1") (pinfunction "1_1") (pintype "passive"))
      (node (ref "R13") (pin "1") (pinfunction "1_1") (pintype "passive"))
      (node (ref "SW1") (pin "3") (pinfunction "3_3") (pintype "passive"))
      (node (ref "U2") (pin "26") (pinfunction "RE1/AN6/PMWR_26") (pintype "bidirectional"))
    )
    (net (code "50") (name "Net-(U2-RE2{slash}AN7{slash}PMCS)") (class "Default")
      (node (ref "R12") (pin "2") (pinfunction "2_2") (pintype "passive"))
      (node (ref "U2") (pin "27") (pinfunction "RE2/AN7/PMCS_27") (pintype "bidirectional"))
    )
    (net (code "51") (name "Net-(U2-VDDCORE{slash}VCAP)") (class "Default")
      (node (ref "C2") (pin "1") (pinfunction "1_1") (pintype "passive"))
      (node (ref "U2") (pin "23") (pinfunction "VDDCORE/VCAP_23") (pintype "bidirectional"))
    )
    (net (code "52") (name "VCC") (class "Default")
      (node (ref "Cin") (pin "1") (pinfunction "1_1") (pintype "passive"))
      (node (ref "J1") (pin "1") (pinfunction "1_1") (pintype "input"))
      (node (ref "J_VCC") (pin "1") (pinfunction "1_1") (pintype "passive"))
      (node (ref "U5V") (pin "1") (pinfunction "IN_1") (pintype "power_in"))
    )
    (net (code "53") (name "unconnected-(ICSP-Pad6)") (class "Default")
      (node (ref "ICSP") (pin "6") (pinfunction "6_6") (pintype "passive+no_connect"))
    )
    (net (code "54") (name "unconnected-(J1-Pad2)") (class "Default")
      (node (ref "J1") (pin "2") (pinfunction "2_2") (pintype "passive"))
    )
    (net (code "55") (name "unconnected-(J2-Pad6)") (class "Default")
      (node (ref "J2") (pin "6") (pinfunction "6_6") (pintype "passive+no_connect"))
    )
    (net (code "56") (name "unconnected-(J2-Pad7)") (class "Default")
      (node (ref "J2") (pin "7") (pinfunction "7_7") (pintype "passive+no_connect"))
    )
    (net (code "57") (name "unconnected-(J2-Pad8)") (class "Default")
      (node (ref "J2") (pin "8") (pinfunction "8_8") (pintype "passive+no_connect"))
    )
    (net (code "58") (name "unconnected-(J2-Pad9)") (class "Default")
      (node (ref "J2") (pin "9") (pinfunction "9_9") (pintype "passive+no_connect"))
    )
    (net (code "59") (name "unconnected-(J2-Pad11)") (class "Default")
      (node (ref "J2") (pin "11") (pinfunction "11_11") (pintype "passive+no_connect"))
    )
    (net (code "60") (name "unconnected-(J2-Pad12)") (class "Default")
      (node (ref "J2") (pin "12") (pinfunction "12_12") (pintype "passive+no_connect"))
    )
    (net (code "61") (name "unconnected-(J2-Pad13)") (class "Default")
      (node (ref "J2") (pin "13") (pinfunction "13_13") (pintype "passive+no_connect"))
    )
    (net (code "62") (name "unconnected-(JCapTemp1-Pad1)") (class "Default")
      (node (ref "JCapTemp1") (pin "1") (pinfunction "1_1") (pintype "passive+no_connect"))
    )
    (net (code "63") (name "unconnected-(JCapTemp2-Pad1)") (class "Default")
      (node (ref "JCapTemp2") (pin "1") (pinfunction "1_1") (pintype "passive+no_connect"))
    )
    (net (code "64") (name "unconnected-(U1-CLKOUT-Pad3)") (class "Default")
      (node (ref "U1") (pin "3") (pinfunction "CLKOUT_3") (pintype "passive+no_connect"))
    )
    (net (code "65") (name "unconnected-(U1-~{INT}-Pad4)") (class "Default")
      (node (ref "U1") (pin "4") (pinfunction "~{INT}_4") (pintype "passive+no_connect"))
    )
    (net (code "66") (name "unconnected-(U2-NC-Pad12)") (class "Default")
      (node (ref "U2") (pin "12") (pinfunction "NC_12") (pintype "passive+no_connect"))
    )
    (net (code "67") (name "unconnected-(U2-NC-Pad13)") (class "Default")
      (node (ref "U2") (pin "13") (pinfunction "NC_13") (pintype "passive+no_connect"))
    )
    (net (code "68") (name "unconnected-(U2-NC-Pad33)") (class "Default")
      (node (ref "U2") (pin "33") (pinfunction "NC_33") (pintype "passive+no_connect"))
    )
    (net (code "69") (name "unconnected-(U2-NC-Pad34)") (class "Default")
      (node (ref "U2") (pin "34") (pinfunction "NC_34") (pintype "passive+no_connect"))
    )
    (net (code "70") (name "unconnected-(U2-RA5{slash}AN4{slash}C1INC{slash}~{SS1}{slash}HLVDIN{slash}RP2-Pad24)") (class "Default")
      (node (ref "U2") (pin "24") (pinfunction "RA5/AN4/C1INC/~{SS1}/HLVDIN/RP2_24") (pintype "bidirectional+no_connect"))
    )
    (net (code "71") (name "unconnected-(U2-RB4{slash}CCP4{slash}PMA1{slash}KBI0{slash}RP7-Pad14)") (class "Default")
      (node (ref "U2") (pin "14") (pinfunction "RB4/CCP4/PMA1/KBI0/RP7_14") (pintype "bidirectional+no_connect"))
    )
    (net (code "72") (name "unconnected-(U2-RB5{slash}CCP5{slash}PMA0{slash}KBI1{slash}RP8-Pad15)") (class "Default")
      (node (ref "U2") (pin "15") (pinfunction "RB5/CCP5/PMA0/KBI1/RP8_15") (pintype "bidirectional+no_connect"))
    )
    (net (code "73") (name "unconnected-(U2-RC0{slash}T1OSO{slash}T1CKI{slash}RP11-Pad32)") (class "Default")
      (node (ref "U2") (pin "32") (pinfunction "RC0/T1OSO/T1CKI/RP11_32") (pintype "bidirectional+no_connect"))
    )
    (net (code "74") (name "unconnected-(U2-RC1{slash}CCP8{slash}T1OSI{slash}RP12-Pad35)") (class "Default")
      (node (ref "U2") (pin "35") (pinfunction "RC1/CCP8/T1OSI/RP12_35") (pintype "bidirectional+no_connect"))
    )
    (net (code "75") (name "unconnected-(U2-RC2{slash}AN11{slash}C2IND{slash}CTPLS{slash}RP13-Pad36)") (class "Default")
      (node (ref "U2") (pin "36") (pinfunction "RC2/AN11/C2IND/CTPLS/RP13_36") (pintype "bidirectional+no_connect"))
    )
  )
)
